# 3_imu.net
KiCad netlist of a schematic drawn in Altium Designer
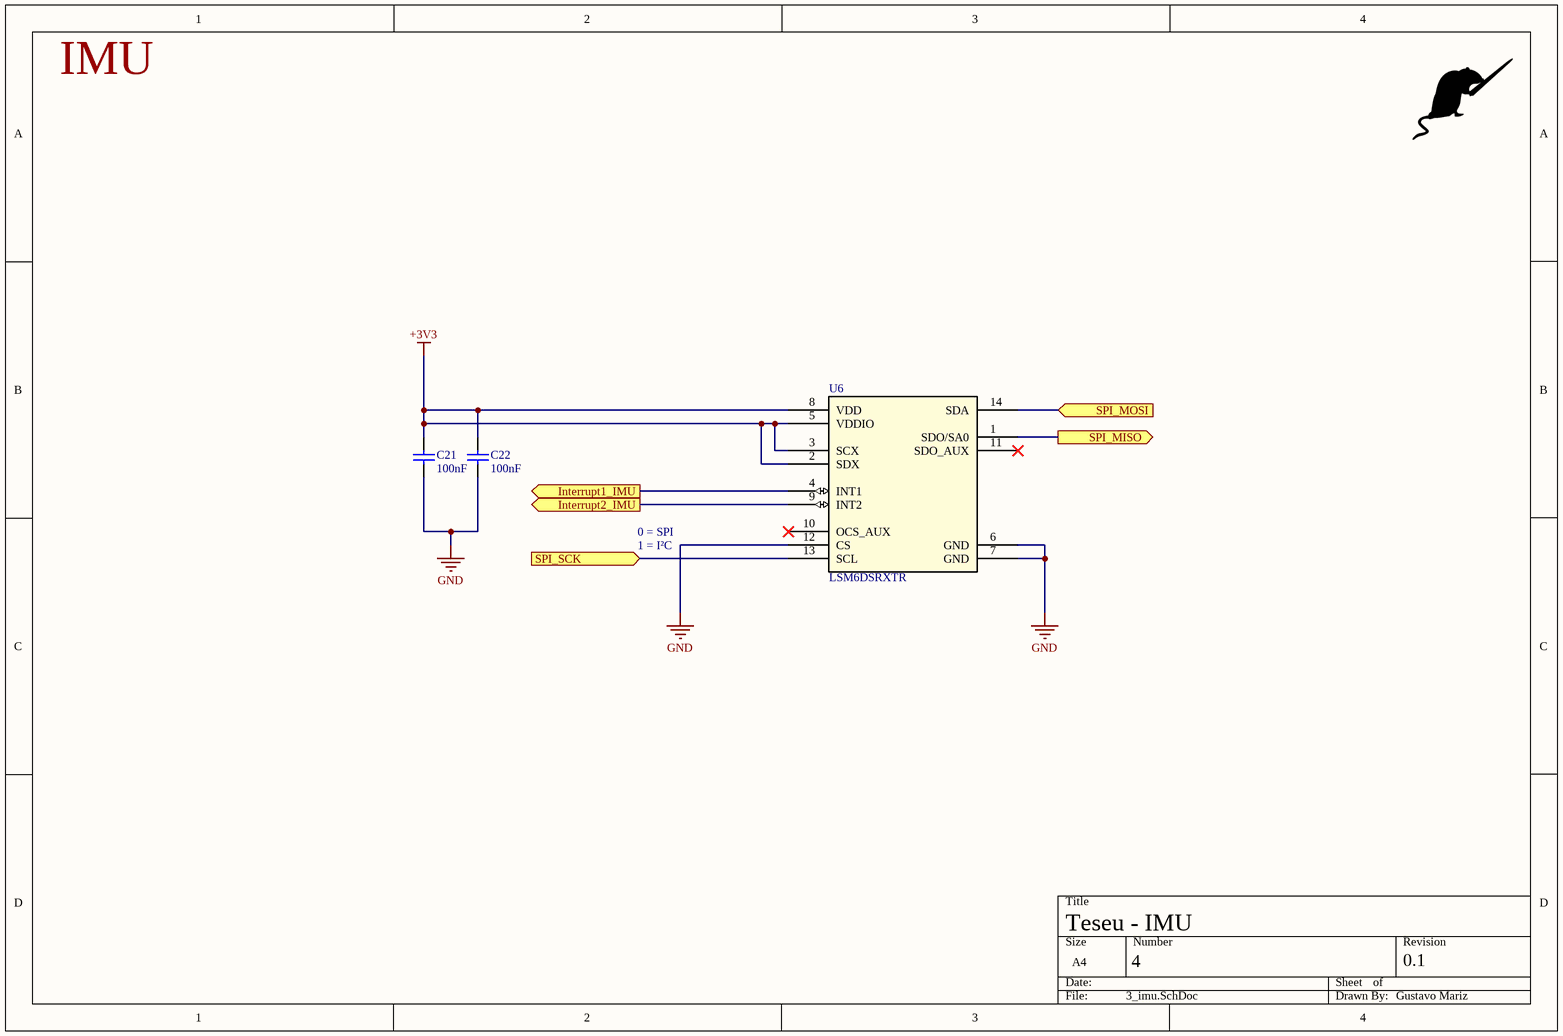
[diagram p0: 3_imu.SchDoc]

(export (version "E")
  (design (tool "Eeschema 10.0.6"))
  (components
    (comp (ref "C21")
      (value "CAP")
      (footprint "0603")
      (description "Capacitor")
      (fields (field (name "VALOR") "100nF"))
      (libsource (lib "Biblioteca Trincabotz (1)") (part "CAP. CERÂMICO"))
    )
    (comp (ref "C22")
      (value "CAP")
      (footprint "0603")
      (description "Capacitor")
      (fields (field (name "VALOR") "100nF"))
      (libsource (lib "Biblioteca Trincabotz (1)") (part "CAP. CERÂMICO"))
    )
    (comp (ref "U6")
      (value "LSM6DSRXTR")
      (footprint "LGA-14L_STM")
      (description "No Description Available")
      (libsource (lib "LSM6DSRXTR") (part "LSM6DSRXTR"))
    )
  )
  (nets
    (net (code "1") (name "+3V3") (class "Default")
      (node (ref "C21") (pin "2") (pinfunction "2_2") (pintype "passive"))
      (node (ref "C22") (pin "2") (pinfunction "2_2") (pintype "passive"))
      (node (ref "U6") (pin "2") (pinfunction "SDX_2") (pintype "passive"))
      (node (ref "U6") (pin "3") (pinfunction "SCX_3") (pintype "passive"))
      (node (ref "U6") (pin "5") (pinfunction "VDDIO_5") (pintype "power_in"))
      (node (ref "U6") (pin "8") (pinfunction "VDD_8") (pintype "power_in"))
    )
    (net (code "2") (name "/Interrupt1_IMU") (class "Default")
      (node (ref "U6") (pin "4") (pinfunction "INT1_4") (pintype "bidirectional"))
    )
    (net (code "3") (name "/Interrupt2_IMU") (class "Default")
      (node (ref "U6") (pin "9") (pinfunction "INT2_9") (pintype "bidirectional"))
    )
    (net (code "4") (name "/SPI_MISO") (class "Default")
      (node (ref "U6") (pin "1") (pinfunction "SDO/SA0_1") (pintype "passive"))
    )
    (net (code "5") (name "/SPI_MOSI") (class "Default")
      (node (ref "U6") (pin "14") (pinfunction "SDA_14") (pintype "passive"))
    )
    (net (code "6") (name "/SPI_SCK") (class "Default")
      (node (ref "U6") (pin "13") (pinfunction "SCL_13") (pintype "passive"))
    )
    (net (code "7") (name "GND") (class "Default")
      (node (ref "C21") (pin "1") (pinfunction "1_1") (pintype "passive"))
      (node (ref "C22") (pin "1") (pinfunction "1_1") (pintype "passive"))
      (node (ref "U6") (pin "12") (pinfunction "CS_12") (pintype "passive"))
      (node (ref "U6") (pin "6") (pinfunction "GND_6") (pintype "power_in"))
      (node (ref "U6") (pin "7") (pinfunction "GND_7") (pintype "power_in"))
    )
    (net (code "8") (name "unconnected-(U6-OCS_AUX-Pad10)") (class "Default")
      (node (ref "U6") (pin "10") (pinfunction "OCS_AUX_10") (pintype "passive+no_connect"))
    )
    (net (code "9") (name "unconnected-(U6-SDO_AUX-Pad11)") (class "Default")
      (node (ref "U6") (pin "11") (pinfunction "SDO_AUX_11") (pintype "passive+no_connect"))
    )
  )
)
